# LifterV01.net
KiCad netlist of a schematic drawn in EAGLE
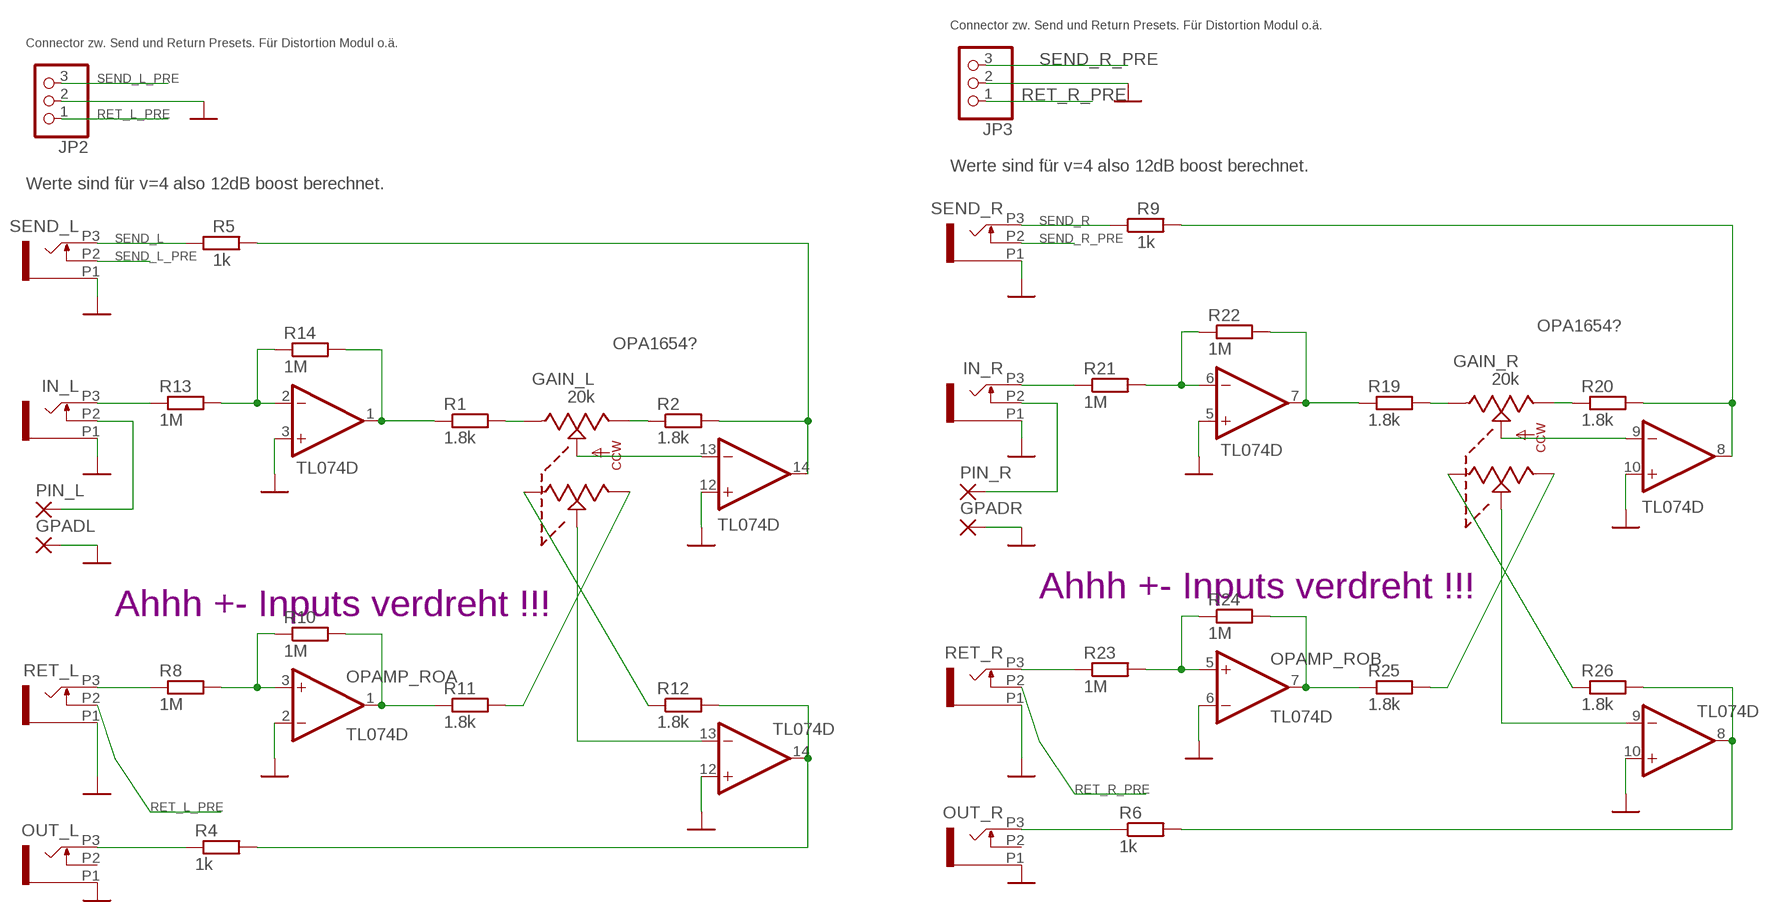
[diagram p0: schematic, sheet 1]
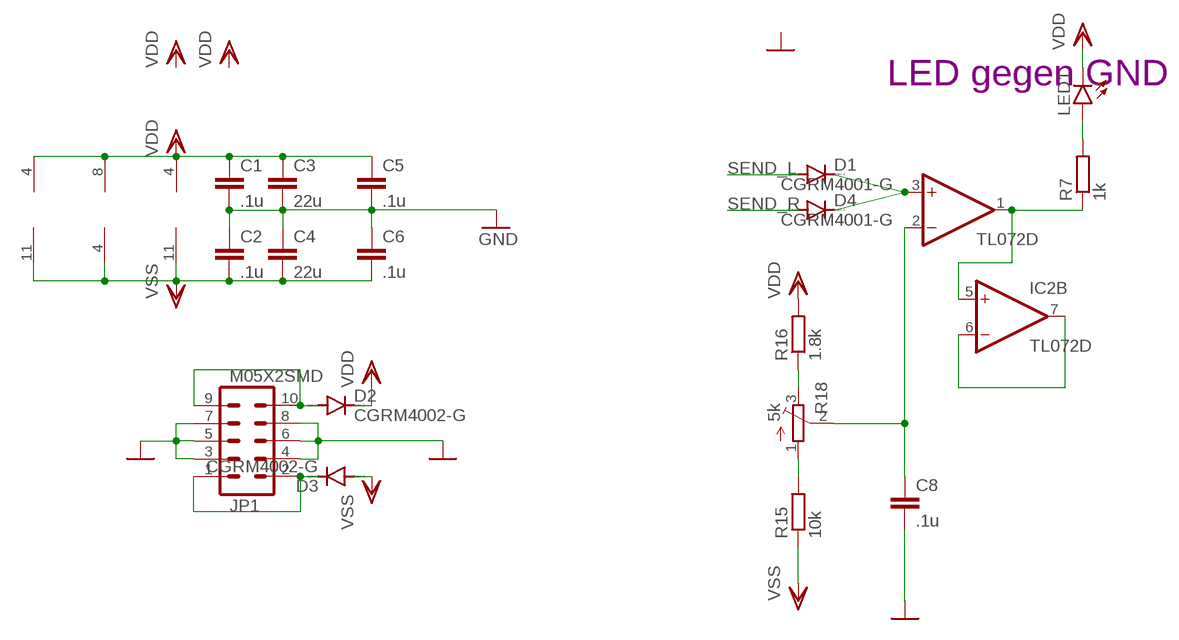
[diagram p1: schematic, sheet 2]

(export (version "E")
  (design (tool "Eeschema 10.0.6"))
  (components
    (comp (ref "GAIN_L")
      (value "20k")
      (footprint "eagle-import:TT_2TAP_VERTICAL")
      (libsource (lib "eagle-import") (part "POT_US_2X"))
    )
    (comp (ref "GAIN_R")
      (value "20k")
      (footprint "eagle-import:TT_2TAP_VERTICAL")
      (libsource (lib "eagle-import") (part "POT_US_2X"))
    )
    (comp (ref "GPADL")
      (value "3,17/1,3")
      (footprint "eagle-import:3,17_1,3")
      (libsource (lib "eagle-import") (part "3,17/1,3"))
    )
    (comp (ref "GPADR")
      (value "3,17/1,3")
      (footprint "eagle-import:3,17_1,3")
      (libsource (lib "eagle-import") (part "3,17/1,3"))
    )
    (comp (ref "IN_L")
      (value "PJ301_THONKICONN6")
      (footprint "eagle-import:WQP_PJ_301M6")
      (libsource (lib "eagle-import") (part "PJ301_THONKICONN6"))
    )
    (comp (ref "IN_R")
      (value "PJ301_THONKICONN6")
      (footprint "eagle-import:WQP_PJ_301M6")
      (libsource (lib "eagle-import") (part "PJ301_THONKICONN6"))
    )
    (comp (ref "JP2")
      (value "PINHD-1X3")
      (footprint "eagle-import:1X03")
      (libsource (lib "eagle-import") (part "PINHD-1X3"))
    )
    (comp (ref "JP3")
      (value "PINHD-1X3")
      (footprint "eagle-import:1X03")
      (libsource (lib "eagle-import") (part "PINHD-1X3"))
    )
    (comp (ref "OPAMP_IS")
      (value "TL074D")
      (footprint "eagle-import:SO14")
      (fields (field (name "SPICEPREFIX") "J"))
      (libsource (lib "eagle-import") (part "TL074D"))
    )
    (comp (ref "OPAMP_RO")
      (value "TL074D")
      (footprint "eagle-import:SO14")
      (fields (field (name "SPICEPREFIX") "J"))
      (libsource (lib "eagle-import") (part "TL074D"))
    )
    (comp (ref "OUT_L")
      (value "PJ301_THONKICONN6")
      (footprint "eagle-import:WQP_PJ_301M6")
      (libsource (lib "eagle-import") (part "PJ301_THONKICONN6"))
    )
    (comp (ref "OUT_R")
      (value "PJ301_THONKICONN6")
      (footprint "eagle-import:WQP_PJ_301M6")
      (libsource (lib "eagle-import") (part "PJ301_THONKICONN6"))
    )
    (comp (ref "PIN_L")
      (value "3,17/1,3")
      (footprint "eagle-import:3,17_1,3")
      (libsource (lib "eagle-import") (part "3,17/1,3"))
    )
    (comp (ref "PIN_R")
      (value "3,17/1,3")
      (footprint "eagle-import:3,17_1,3")
      (libsource (lib "eagle-import") (part "3,17/1,3"))
    )
    (comp (ref "R1")
      (value "1.8k")
      (footprint "eagle-import:R0603")
      (libsource (lib "eagle-import") (part "R-EU_R0603"))
    )
    (comp (ref "R2")
      (value "1.8k")
      (footprint "eagle-import:R0603")
      (libsource (lib "eagle-import") (part "R-EU_R0603"))
    )
    (comp (ref "R4")
      (value "1k")
      (footprint "eagle-import:R0603")
      (libsource (lib "eagle-import") (part "R-EU_R0603"))
    )
    (comp (ref "R5")
      (value "1k")
      (footprint "eagle-import:R0603")
      (libsource (lib "eagle-import") (part "R-EU_R0603"))
    )
    (comp (ref "R6")
      (value "1k")
      (footprint "eagle-import:R0603")
      (libsource (lib "eagle-import") (part "R-EU_R0603"))
    )
    (comp (ref "R8")
      (value "1M")
      (footprint "eagle-import:R0603")
      (libsource (lib "eagle-import") (part "R-EU_R0603"))
    )
    (comp (ref "R9")
      (value "1k")
      (footprint "eagle-import:R0603")
      (libsource (lib "eagle-import") (part "R-EU_R0603"))
    )
    (comp (ref "R10")
      (value "1M")
      (footprint "eagle-import:R0603")
      (libsource (lib "eagle-import") (part "R-EU_R0603"))
    )
    (comp (ref "R11")
      (value "1.8k")
      (footprint "eagle-import:R0603")
      (libsource (lib "eagle-import") (part "R-EU_R0603"))
    )
    (comp (ref "R12")
      (value "1.8k")
      (footprint "eagle-import:R0603")
      (libsource (lib "eagle-import") (part "R-EU_R0603"))
    )
    (comp (ref "R13")
      (value "1M")
      (footprint "eagle-import:R0603")
      (libsource (lib "eagle-import") (part "R-EU_R0603"))
    )
    (comp (ref "R14")
      (value "1M")
      (footprint "eagle-import:R0603")
      (libsource (lib "eagle-import") (part "R-EU_R0603"))
    )
    (comp (ref "R19")
      (value "1.8k")
      (footprint "eagle-import:R0603")
      (libsource (lib "eagle-import") (part "R-EU_R0603"))
    )
    (comp (ref "R20")
      (value "1.8k")
      (footprint "eagle-import:R0603")
      (libsource (lib "eagle-import") (part "R-EU_R0603"))
    )
    (comp (ref "R21")
      (value "1M")
      (footprint "eagle-import:R0603")
      (libsource (lib "eagle-import") (part "R-EU_R0603"))
    )
    (comp (ref "R22")
      (value "1M")
      (footprint "eagle-import:R0603")
      (libsource (lib "eagle-import") (part "R-EU_R0603"))
    )
    (comp (ref "R23")
      (value "1M")
      (footprint "eagle-import:R0603")
      (libsource (lib "eagle-import") (part "R-EU_R0603"))
    )
    (comp (ref "R24")
      (value "1M")
      (footprint "eagle-import:R0603")
      (libsource (lib "eagle-import") (part "R-EU_R0603"))
    )
    (comp (ref "R25")
      (value "1.8k")
      (footprint "eagle-import:R0603")
      (libsource (lib "eagle-import") (part "R-EU_R0603"))
    )
    (comp (ref "R26")
      (value "1.8k")
      (footprint "eagle-import:R0603")
      (libsource (lib "eagle-import") (part "R-EU_R0603"))
    )
    (comp (ref "RET_L")
      (value "PJ301_THONKICONN6")
      (footprint "eagle-import:WQP_PJ_301M6")
      (libsource (lib "eagle-import") (part "PJ301_THONKICONN6"))
    )
    (comp (ref "RET_R")
      (value "PJ301_THONKICONN6")
      (footprint "eagle-import:WQP_PJ_301M6")
      (libsource (lib "eagle-import") (part "PJ301_THONKICONN6"))
    )
    (comp (ref "SEND_L")
      (value "PJ301_THONKICONN6")
      (footprint "eagle-import:WQP_PJ_301M6")
      (libsource (lib "eagle-import") (part "PJ301_THONKICONN6"))
    )
    (comp (ref "SEND_R")
      (value "PJ301_THONKICONN6")
      (footprint "eagle-import:WQP_PJ_301M6")
      (libsource (lib "eagle-import") (part "PJ301_THONKICONN6"))
    )
    (comp (ref "C1")
      (value ".1u")
      (footprint "eagle-import:C0603")
      (libsource (lib "eagle-import") (part "C-EUC0603"))
    )
    (comp (ref "C2")
      (value ".1u")
      (footprint "eagle-import:C0603")
      (libsource (lib "eagle-import") (part "C-EUC0603"))
    )
    (comp (ref "C3")
      (value "22u")
      (footprint "eagle-import:C1210")
      (libsource (lib "eagle-import") (part "C-EUC1210"))
    )
    (comp (ref "C4")
      (value "22u")
      (footprint "eagle-import:C1210")
      (libsource (lib "eagle-import") (part "C-EUC1210"))
    )
    (comp (ref "C5")
      (value ".1u")
      (footprint "eagle-import:C0603")
      (libsource (lib "eagle-import") (part "C-EUC0603"))
    )
    (comp (ref "C6")
      (value ".1u")
      (footprint "eagle-import:C0603")
      (libsource (lib "eagle-import") (part "C-EUC0603"))
    )
    (comp (ref "C8")
      (value ".1u")
      (footprint "eagle-import:C0603")
      (libsource (lib "eagle-import") (part "C-EUC0603"))
    )
    (comp (ref "D1")
      (value "CGRM4001-G")
      (footprint "eagle-import:SOD-123_MINI-SMA")
      (libsource (lib "eagle-import") (part "CGRM400-G1"))
    )
    (comp (ref "D2")
      (value "CGRM4002-G")
      (footprint "eagle-import:SOD-123_MINI-SMA")
      (libsource (lib "eagle-import") (part "CGRM400-G2"))
    )
    (comp (ref "D3")
      (value "CGRM4002-G")
      (footprint "eagle-import:SOD-123_MINI-SMA")
      (libsource (lib "eagle-import") (part "CGRM400-G2"))
    )
    (comp (ref "D4")
      (value "CGRM4001-G")
      (footprint "eagle-import:SOD-123_MINI-SMA")
      (libsource (lib "eagle-import") (part "CGRM400-G1"))
    )
    (comp (ref "IC2")
      (value "TL072D")
      (footprint "eagle-import:SO08")
      (libsource (lib "eagle-import") (part "TL072D"))
    )
    (comp (ref "JP1")
      (value "M05X2SMD")
      (footprint "eagle-import:2X5-SMD")
      (libsource (lib "eagle-import") (part "M05X2SMD"))
    )
    (comp (ref "LED1")
      (value "LED3MM")
      (footprint "eagle-import:LED3MM")
      (libsource (lib "eagle-import") (part "LED3MM"))
    )
    (comp (ref "R7")
      (value "1k")
      (footprint "eagle-import:R0603")
      (libsource (lib "eagle-import") (part "R-EU_R0603"))
    )
    (comp (ref "R15")
      (value "10k")
      (footprint "eagle-import:R0603")
      (libsource (lib "eagle-import") (part "R-EU_R0603"))
    )
    (comp (ref "R16")
      (value "1.8k")
      (footprint "eagle-import:R0603")
      (libsource (lib "eagle-import") (part "R-EU_R0603"))
    )
    (comp (ref "R18")
      (value "5k")
      (footprint "eagle-import:3223G")
      (libsource (lib "eagle-import") (part "TRIM_EU-3223G"))
    )
  )
  (nets
    (net (code "1") (name "GND") (class "Default")
      (node (ref "C1") (pin "2") (pinfunction "2_2") (pintype "passive"))
      (node (ref "C2") (pin "1") (pinfunction "1_1") (pintype "passive"))
      (node (ref "C3") (pin "2") (pinfunction "2_2") (pintype "passive"))
      (node (ref "C4") (pin "1") (pinfunction "1_1") (pintype "passive"))
      (node (ref "C5") (pin "2") (pinfunction "2_2") (pintype "passive"))
      (node (ref "C6") (pin "1") (pinfunction "1_1") (pintype "passive"))
      (node (ref "C8") (pin "2") (pinfunction "2_2") (pintype "passive"))
      (node (ref "GPADL") (pin "1") (pinfunction "P_1") (pintype "passive"))
      (node (ref "GPADR") (pin "1") (pinfunction "P_1") (pintype "passive"))
      (node (ref "IN_L") (pin "P1") (pinfunction "1_P1") (pintype "passive"))
      (node (ref "IN_R") (pin "P1") (pinfunction "1_P1") (pintype "passive"))
      (node (ref "JP1") (pin "3") (pinfunction "3_3") (pintype "passive"))
      (node (ref "JP1") (pin "4") (pinfunction "4_4") (pintype "passive"))
      (node (ref "JP1") (pin "5") (pinfunction "5_5") (pintype "passive"))
      (node (ref "JP1") (pin "6") (pinfunction "6_6") (pintype "passive"))
      (node (ref "JP1") (pin "7") (pinfunction "7_7") (pintype "passive"))
      (node (ref "JP1") (pin "8") (pinfunction "8_8") (pintype "passive"))
      (node (ref "JP2") (pin "2") (pinfunction "2_2") (pintype "passive"))
      (node (ref "JP3") (pin "2") (pinfunction "2_2") (pintype "passive"))
      (node (ref "OPAMP_IS") (pin "10") (pinfunction "+IN_10") (pintype "input"))
      (node (ref "OPAMP_IS") (pin "12") (pinfunction "+IN_12") (pintype "input"))
      (node (ref "OPAMP_IS") (pin "3") (pinfunction "+IN_3") (pintype "input"))
      (node (ref "OPAMP_IS") (pin "5") (pinfunction "+IN_5") (pintype "input"))
      (node (ref "OPAMP_RO") (pin "10") (pinfunction "+IN_10") (pintype "input"))
      (node (ref "OPAMP_RO") (pin "12") (pinfunction "+IN_12") (pintype "input"))
      (node (ref "OPAMP_RO") (pin "2") (pinfunction "-IN_2") (pintype "input"))
      (node (ref "OPAMP_RO") (pin "6") (pinfunction "-IN_6") (pintype "input"))
      (node (ref "OUT_L") (pin "P1") (pinfunction "1_P1") (pintype "passive"))
      (node (ref "OUT_R") (pin "P1") (pinfunction "1_P1") (pintype "passive"))
      (node (ref "RET_L") (pin "P1") (pinfunction "1_P1") (pintype "passive"))
      (node (ref "RET_R") (pin "P1") (pinfunction "1_P1") (pintype "passive"))
      (node (ref "SEND_L") (pin "P1") (pinfunction "1_P1") (pintype "passive"))
      (node (ref "SEND_R") (pin "P1") (pinfunction "1_P1") (pintype "passive"))
    )
    (net (code "2") (name "Net-(D2-PadA)") (class "Default")
      (node (ref "D2") (pin "A") (pinfunction "A_A") (pintype "passive"))
      (node (ref "JP1") (pin "10") (pinfunction "10_10") (pintype "passive"))
      (node (ref "JP1") (pin "9") (pinfunction "9_9") (pintype "passive"))
    )
    (net (code "3") (name "Net-(D3-PadC)") (class "Default")
      (node (ref "D3") (pin "C") (pinfunction "C_C") (pintype "passive"))
      (node (ref "JP1") (pin "1") (pinfunction "1_1") (pintype "passive"))
      (node (ref "JP1") (pin "2") (pinfunction "2_2") (pintype "passive"))
    )
    (net (code "4") (name "Net-(GAIN_L-PadCCW)") (class "Default")
      (node (ref "GAIN_L") (pin "CCW") (pinfunction "CCW_CCW") (pintype "passive"))
      (node (ref "R2") (pin "1") (pinfunction "1_1") (pintype "passive"))
    )
    (net (code "5") (name "Net-(GAIN_L-PadCCW1)") (class "Default")
      (node (ref "GAIN_L") (pin "CCW1") (pinfunction "CCW1_CCW1") (pintype "passive"))
      (node (ref "R11") (pin "2") (pinfunction "2_2") (pintype "passive"))
    )
    (net (code "6") (name "Net-(GAIN_L-PadCW)") (class "Default")
      (node (ref "GAIN_L") (pin "CW") (pinfunction "CW_CW") (pintype "passive"))
      (node (ref "R1") (pin "2") (pinfunction "2_2") (pintype "passive"))
    )
    (net (code "7") (name "Net-(GAIN_L-PadCW1)") (class "Default")
      (node (ref "GAIN_L") (pin "CW1") (pinfunction "CW1_CW1") (pintype "passive"))
      (node (ref "R12") (pin "1") (pinfunction "1_1") (pintype "passive"))
    )
    (net (code "8") (name "Net-(GAIN_R-PadCCW)") (class "Default")
      (node (ref "GAIN_R") (pin "CCW") (pinfunction "CCW_CCW") (pintype "passive"))
      (node (ref "R20") (pin "1") (pinfunction "1_1") (pintype "passive"))
    )
    (net (code "9") (name "Net-(GAIN_R-PadCCW1)") (class "Default")
      (node (ref "GAIN_R") (pin "CCW1") (pinfunction "CCW1_CCW1") (pintype "passive"))
      (node (ref "R25") (pin "2") (pinfunction "2_2") (pintype "passive"))
    )
    (net (code "10") (name "Net-(GAIN_R-PadCW)") (class "Default")
      (node (ref "GAIN_R") (pin "CW") (pinfunction "CW_CW") (pintype "passive"))
      (node (ref "R19") (pin "2") (pinfunction "2_2") (pintype "passive"))
    )
    (net (code "11") (name "Net-(GAIN_R-PadCW1)") (class "Default")
      (node (ref "GAIN_R") (pin "CW1") (pinfunction "CW1_CW1") (pintype "passive"))
      (node (ref "R26") (pin "1") (pinfunction "1_1") (pintype "passive"))
    )
    (net (code "12") (name "Net-(IC2A-+IN)") (class "Default")
      (node (ref "D1") (pin "C") (pinfunction "C_C") (pintype "passive"))
      (node (ref "D4") (pin "C") (pinfunction "C_C") (pintype "passive"))
      (node (ref "IC2") (pin "3") (pinfunction "+IN_3") (pintype "input"))
    )
    (net (code "13") (name "Net-(IC2A--IN)") (class "Default")
      (node (ref "C8") (pin "1") (pinfunction "1_1") (pintype "passive"))
      (node (ref "IC2") (pin "2") (pinfunction "-IN_2") (pintype "input"))
      (node (ref "R18") (pin "2") (pinfunction "S_2") (pintype "passive"))
    )
    (net (code "14") (name "Net-(IC2A-OUT)") (class "Default")
      (node (ref "IC2") (pin "1") (pinfunction "OUT_1") (pintype "output"))
      (node (ref "IC2") (pin "5") (pinfunction "+IN_5") (pintype "input"))
      (node (ref "R7") (pin "1") (pinfunction "1_1") (pintype "passive"))
    )
    (net (code "15") (name "Net-(IC2B--IN)") (class "Default")
      (node (ref "IC2") (pin "6") (pinfunction "-IN_6") (pintype "input"))
      (node (ref "IC2") (pin "7") (pinfunction "OUT_7") (pintype "output"))
    )
    (net (code "16") (name "Net-(IN_L-2)") (class "Default")
      (node (ref "IN_L") (pin "P2") (pinfunction "2_P2") (pintype "passive"))
      (node (ref "PIN_L") (pin "1") (pinfunction "P_1") (pintype "passive"))
    )
    (net (code "17") (name "Net-(IN_L-3)") (class "Default")
      (node (ref "IN_L") (pin "P3") (pinfunction "3_P3") (pintype "passive"))
      (node (ref "R13") (pin "1") (pinfunction "1_1") (pintype "passive"))
    )
    (net (code "18") (name "Net-(IN_R-2)") (class "Default")
      (node (ref "IN_R") (pin "P2") (pinfunction "2_P2") (pintype "passive"))
      (node (ref "PIN_R") (pin "1") (pinfunction "P_1") (pintype "passive"))
    )
    (net (code "19") (name "Net-(IN_R-3)") (class "Default")
      (node (ref "IN_R") (pin "P3") (pinfunction "3_P3") (pintype "passive"))
      (node (ref "R21") (pin "1") (pinfunction "1_1") (pintype "passive"))
    )
    (net (code "20") (name "Net-(LED1-PadA)") (class "Default")
      (node (ref "LED1") (pin "A") (pinfunction "A_A") (pintype "passive"))
      (node (ref "R7") (pin "2") (pinfunction "2_2") (pintype "passive"))
    )
    (net (code "21") (name "Net-(OPAMP_ISA--IN)") (class "Default")
      (node (ref "OPAMP_IS") (pin "2") (pinfunction "-IN_2") (pintype "input"))
      (node (ref "R13") (pin "2") (pinfunction "2_2") (pintype "passive"))
      (node (ref "R14") (pin "1") (pinfunction "1_1") (pintype "passive"))
    )
    (net (code "22") (name "Net-(OPAMP_ISA-OUT)") (class "Default")
      (node (ref "OPAMP_IS") (pin "1") (pinfunction "OUT_1") (pintype "output"))
      (node (ref "R1") (pin "1") (pinfunction "1_1") (pintype "passive"))
      (node (ref "R14") (pin "2") (pinfunction "2_2") (pintype "passive"))
    )
    (net (code "23") (name "Net-(OPAMP_ISB--IN)") (class "Default")
      (node (ref "OPAMP_IS") (pin "6") (pinfunction "-IN_6") (pintype "input"))
      (node (ref "R21") (pin "2") (pinfunction "2_2") (pintype "passive"))
      (node (ref "R22") (pin "1") (pinfunction "1_1") (pintype "passive"))
    )
    (net (code "24") (name "Net-(OPAMP_ISB-OUT)") (class "Default")
      (node (ref "OPAMP_IS") (pin "7") (pinfunction "OUT_7") (pintype "output"))
      (node (ref "R19") (pin "1") (pinfunction "1_1") (pintype "passive"))
      (node (ref "R22") (pin "2") (pinfunction "2_2") (pintype "passive"))
    )
    (net (code "25") (name "Net-(OPAMP_ISC--IN)") (class "Default")
      (node (ref "GAIN_R") (pin "CENTER") (pinfunction "CENTER_CENTER") (pintype "passive"))
      (node (ref "OPAMP_IS") (pin "9") (pinfunction "-IN_9") (pintype "input"))
    )
    (net (code "26") (name "Net-(OPAMP_ISC-OUT)") (class "Default")
      (node (ref "OPAMP_IS") (pin "8") (pinfunction "OUT_8") (pintype "output"))
      (node (ref "R20") (pin "2") (pinfunction "2_2") (pintype "passive"))
      (node (ref "R9") (pin "2") (pinfunction "2_2") (pintype "passive"))
    )
    (net (code "27") (name "Net-(OPAMP_ISD--IN)") (class "Default")
      (node (ref "GAIN_L") (pin "CENTER") (pinfunction "CENTER_CENTER") (pintype "passive"))
      (node (ref "OPAMP_IS") (pin "13") (pinfunction "-IN_13") (pintype "input"))
    )
    (net (code "28") (name "Net-(OPAMP_ISD-OUT)") (class "Default")
      (node (ref "OPAMP_IS") (pin "14") (pinfunction "OUT_14") (pintype "output"))
      (node (ref "R2") (pin "2") (pinfunction "2_2") (pintype "passive"))
      (node (ref "R5") (pin "2") (pinfunction "2_2") (pintype "passive"))
    )
    (net (code "29") (name "Net-(OPAMP_ROA-+IN)") (class "Default")
      (node (ref "OPAMP_RO") (pin "3") (pinfunction "+IN_3") (pintype "input"))
      (node (ref "R10") (pin "1") (pinfunction "1_1") (pintype "passive"))
      (node (ref "R8") (pin "2") (pinfunction "2_2") (pintype "passive"))
    )
    (net (code "30") (name "Net-(OPAMP_ROA-OUT)") (class "Default")
      (node (ref "OPAMP_RO") (pin "1") (pinfunction "OUT_1") (pintype "output"))
      (node (ref "R10") (pin "2") (pinfunction "2_2") (pintype "passive"))
      (node (ref "R11") (pin "1") (pinfunction "1_1") (pintype "passive"))
    )
    (net (code "31") (name "Net-(OPAMP_ROB-+IN)") (class "Default")
      (node (ref "OPAMP_RO") (pin "5") (pinfunction "+IN_5") (pintype "input"))
      (node (ref "R23") (pin "2") (pinfunction "2_2") (pintype "passive"))
      (node (ref "R24") (pin "1") (pinfunction "1_1") (pintype "passive"))
    )
    (net (code "32") (name "Net-(OPAMP_ROB-OUT)") (class "Default")
      (node (ref "OPAMP_RO") (pin "7") (pinfunction "OUT_7") (pintype "output"))
      (node (ref "R24") (pin "2") (pinfunction "2_2") (pintype "passive"))
      (node (ref "R25") (pin "1") (pinfunction "1_1") (pintype "passive"))
    )
    (net (code "33") (name "Net-(OPAMP_ROC--IN)") (class "Default")
      (node (ref "GAIN_R") (pin "CENTER1") (pinfunction "CENTER1_CENTER1") (pintype "passive"))
      (node (ref "OPAMP_RO") (pin "9") (pinfunction "-IN_9") (pintype "input"))
    )
    (net (code "34") (name "Net-(OPAMP_ROC-OUT)") (class "Default")
      (node (ref "OPAMP_RO") (pin "8") (pinfunction "OUT_8") (pintype "output"))
      (node (ref "R26") (pin "2") (pinfunction "2_2") (pintype "passive"))
      (node (ref "R6") (pin "2") (pinfunction "2_2") (pintype "passive"))
    )
    (net (code "35") (name "Net-(OPAMP_ROD--IN)") (class "Default")
      (node (ref "GAIN_L") (pin "CENTER1") (pinfunction "CENTER1_CENTER1") (pintype "passive"))
      (node (ref "OPAMP_RO") (pin "13") (pinfunction "-IN_13") (pintype "input"))
    )
    (net (code "36") (name "Net-(OPAMP_ROD-OUT)") (class "Default")
      (node (ref "OPAMP_RO") (pin "14") (pinfunction "OUT_14") (pintype "output"))
      (node (ref "R12") (pin "2") (pinfunction "2_2") (pintype "passive"))
      (node (ref "R4") (pin "2") (pinfunction "2_2") (pintype "passive"))
    )
    (net (code "37") (name "Net-(OUT_L-3)") (class "Default")
      (node (ref "OUT_L") (pin "P3") (pinfunction "3_P3") (pintype "passive"))
      (node (ref "R4") (pin "1") (pinfunction "1_1") (pintype "passive"))
    )
    (net (code "38") (name "Net-(OUT_R-3)") (class "Default")
      (node (ref "OUT_R") (pin "P3") (pinfunction "3_P3") (pintype "passive"))
      (node (ref "R6") (pin "1") (pinfunction "1_1") (pintype "passive"))
    )
    (net (code "39") (name "Net-(R18-A)") (class "Default")
      (node (ref "R15") (pin "2") (pinfunction "2_2") (pintype "passive"))
      (node (ref "R18") (pin "1") (pinfunction "A_1") (pintype "passive"))
    )
    (net (code "40") (name "Net-(R18-E)") (class "Default")
      (node (ref "R16") (pin "1") (pinfunction "1_1") (pintype "passive"))
      (node (ref "R18") (pin "3") (pinfunction "E_3") (pintype "passive"))
    )
    (net (code "41") (name "Net-(RET_L-3)") (class "Default")
      (node (ref "R8") (pin "1") (pinfunction "1_1") (pintype "passive"))
      (node (ref "RET_L") (pin "P3") (pinfunction "3_P3") (pintype "passive"))
    )
    (net (code "42") (name "Net-(RET_R-3)") (class "Default")
      (node (ref "R23") (pin "1") (pinfunction "1_1") (pintype "passive"))
      (node (ref "RET_R") (pin "P3") (pinfunction "3_P3") (pintype "passive"))
    )
    (net (code "43") (name "RET_L_PRE") (class "Default")
      (node (ref "JP2") (pin "1") (pinfunction "1_1") (pintype "passive"))
      (node (ref "RET_L") (pin "P2") (pinfunction "2_P2") (pintype "passive"))
    )
    (net (code "44") (name "RET_R_PRE") (class "Default")
      (node (ref "JP3") (pin "1") (pinfunction "1_1") (pintype "passive"))
      (node (ref "RET_R") (pin "P2") (pinfunction "2_P2") (pintype "passive"))
    )
    (net (code "45") (name "SEND_L") (class "Default")
      (node (ref "D1") (pin "A") (pinfunction "A_A") (pintype "passive"))
      (node (ref "R5") (pin "1") (pinfunction "1_1") (pintype "passive"))
      (node (ref "SEND_L") (pin "P3") (pinfunction "3_P3") (pintype "passive"))
    )
    (net (code "46") (name "SEND_L_PRE") (class "Default")
      (node (ref "JP2") (pin "3") (pinfunction "3_3") (pintype "passive"))
      (node (ref "SEND_L") (pin "P2") (pinfunction "2_P2") (pintype "passive"))
    )
    (net (code "47") (name "SEND_R") (class "Default")
      (node (ref "D4") (pin "A") (pinfunction "A_A") (pintype "passive"))
      (node (ref "R9") (pin "1") (pinfunction "1_1") (pintype "passive"))
      (node (ref "SEND_R") (pin "P3") (pinfunction "3_P3") (pintype "passive"))
    )
    (net (code "48") (name "SEND_R_PRE") (class "Default")
      (node (ref "JP3") (pin "3") (pinfunction "3_3") (pintype "passive"))
      (node (ref "SEND_R") (pin "P2") (pinfunction "2_P2") (pintype "passive"))
    )
    (net (code "49") (name "VDD") (class "Default")
      (node (ref "C1") (pin "1") (pinfunction "1_1") (pintype "passive"))
      (node (ref "C3") (pin "1") (pinfunction "1_1") (pintype "passive"))
      (node (ref "C5") (pin "1") (pinfunction "1_1") (pintype "passive"))
      (node (ref "D2") (pin "C") (pinfunction "C_C") (pintype "passive"))
      (node (ref "IC2") (pin "8") (pinfunction "V+_8") (pintype "power_in"))
      (node (ref "LED1") (pin "K") (pinfunction "C_K") (pintype "passive"))
      (node (ref "OPAMP_IS") (pin "4") (pinfunction "V+_4") (pintype "power_in"))
      (node (ref "OPAMP_RO") (pin "4") (pinfunction "V+_4") (pintype "power_in"))
      (node (ref "R16") (pin "2") (pinfunction "2_2") (pintype "passive"))
    )
    (net (code "50") (name "VSS") (class "Default")
      (node (ref "C2") (pin "2") (pinfunction "2_2") (pintype "passive"))
      (node (ref "C4") (pin "2") (pinfunction "2_2") (pintype "passive"))
      (node (ref "C6") (pin "2") (pinfunction "2_2") (pintype "passive"))
      (node (ref "D3") (pin "A") (pinfunction "A_A") (pintype "passive"))
      (node (ref "IC2") (pin "4") (pinfunction "V-_4") (pintype "power_in"))
      (node (ref "OPAMP_IS") (pin "11") (pinfunction "V-_11") (pintype "power_in"))
      (node (ref "OPAMP_RO") (pin "11") (pinfunction "V-_11") (pintype "power_in"))
      (node (ref "R15") (pin "1") (pinfunction "1_1") (pintype "passive"))
    )
    (net (code "51") (name "unconnected-(OUT_L-2-PadP2)") (class "Default")
      (node (ref "OUT_L") (pin "P2") (pinfunction "2_P2") (pintype "passive"))
    )
    (net (code "52") (name "unconnected-(OUT_R-2-PadP2)") (class "Default")
      (node (ref "OUT_R") (pin "P2") (pinfunction "2_P2") (pintype "passive"))
    )
  )
)
